# V-00757-01.net
KiCad netlist of a schematic drawn in EAGLE
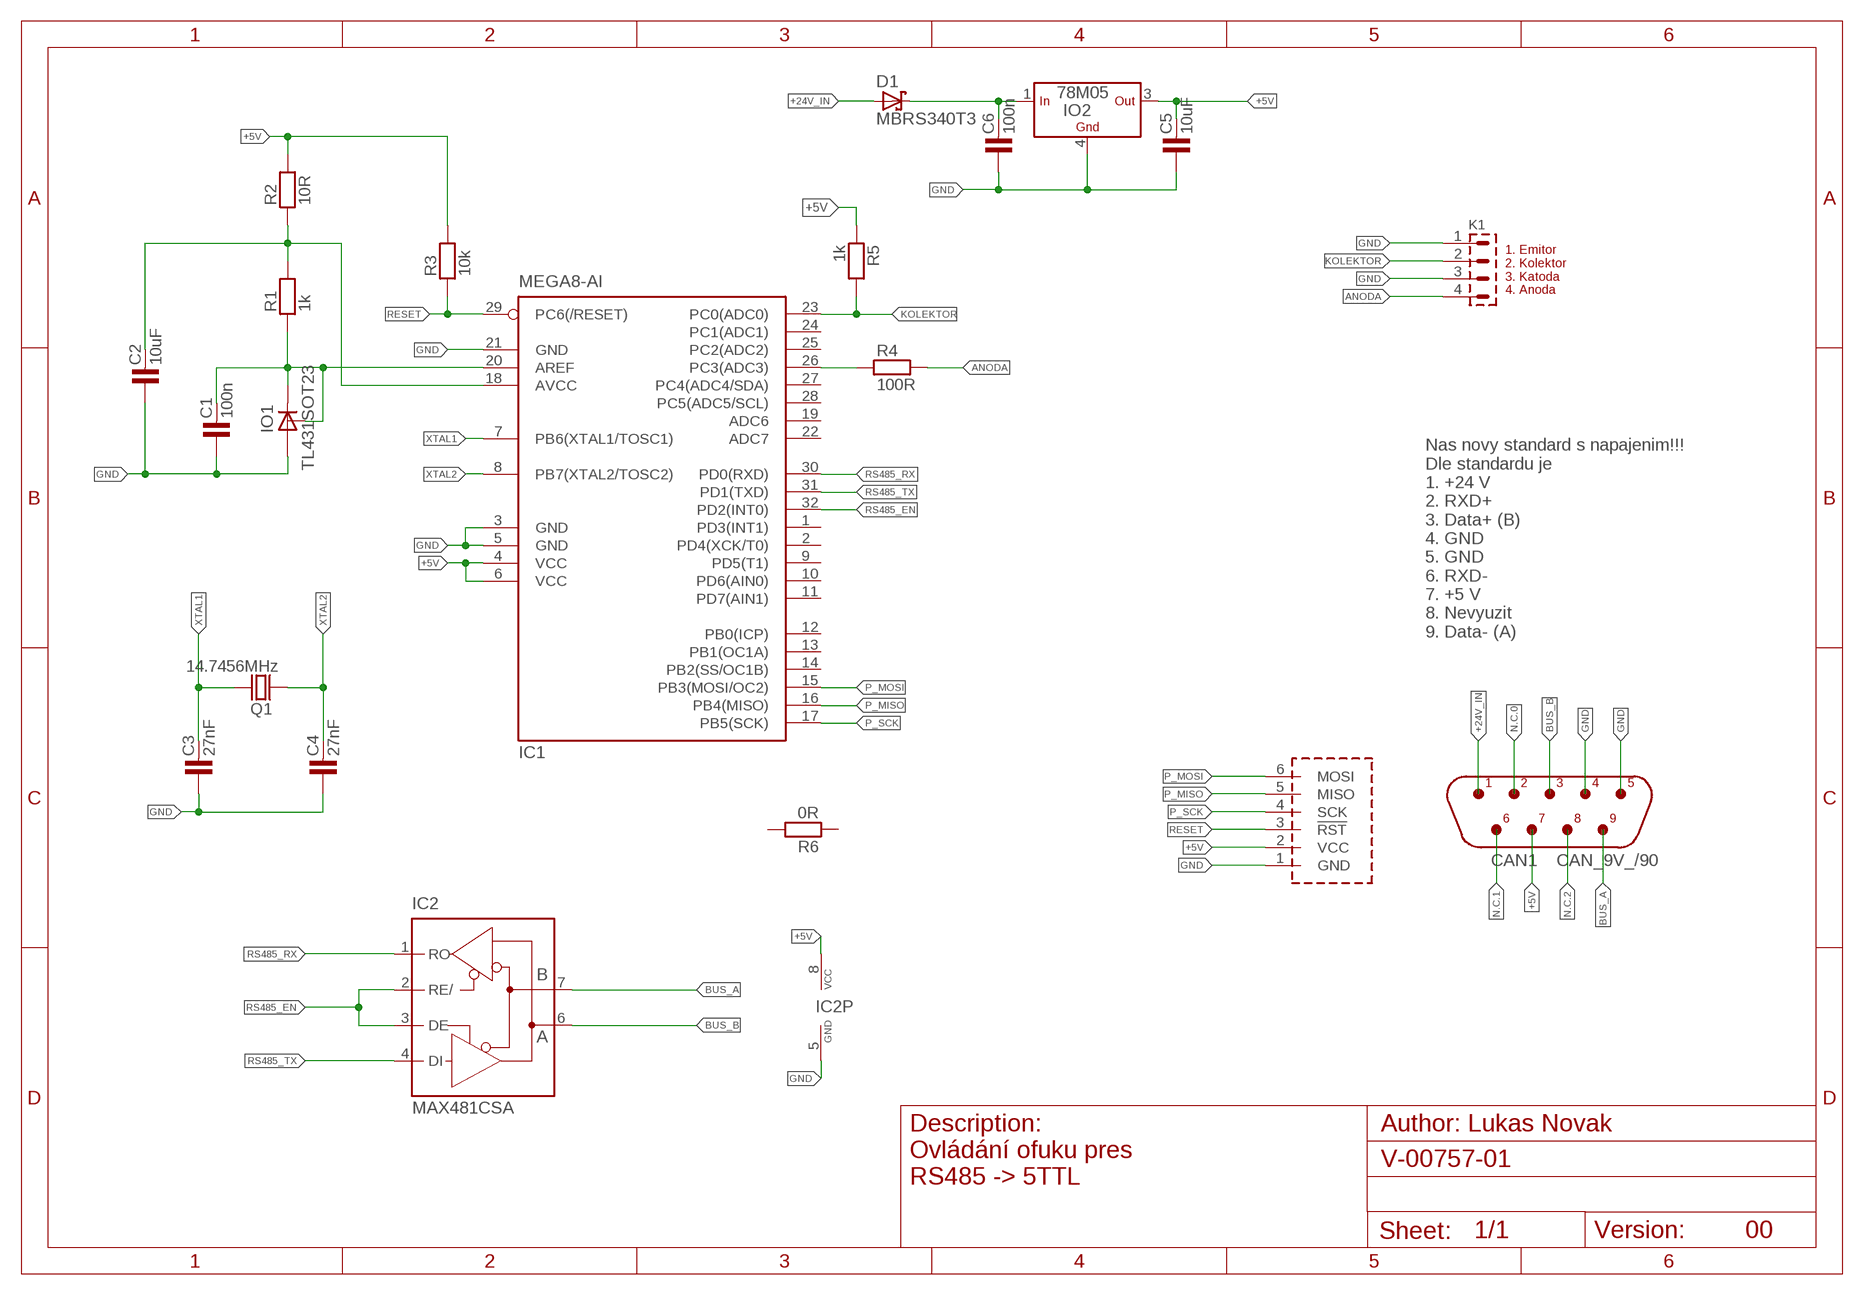
[diagram p0: schematic, sheet 1]

(export (version "E")
  (design (tool "Eeschema 10.0.6"))
  (components
    (comp (ref "C1")
      (value "100n")
      (footprint "eagle-import:1206")
      (libsource (lib "eagle-import") (part "C-KER_1206"))
    )
    (comp (ref "C2")
      (value "10uF")
      (footprint "eagle-import:1206")
      (libsource (lib "eagle-import") (part "C-KER_1206"))
    )
    (comp (ref "C3")
      (value "27nF")
      (footprint "eagle-import:0805")
      (libsource (lib "eagle-import") (part "C-KER_0805"))
    )
    (comp (ref "C4")
      (value "27nF")
      (footprint "eagle-import:0805")
      (libsource (lib "eagle-import") (part "C-KER_0805"))
    )
    (comp (ref "C5")
      (value "10uF")
      (footprint "eagle-import:1206")
      (libsource (lib "eagle-import") (part "C-KER_1206"))
    )
    (comp (ref "C6")
      (value "100n")
      (footprint "eagle-import:1206")
      (libsource (lib "eagle-import") (part "C-KER_1206"))
    )
    (comp (ref "CAN1")
      (value "CAN_9V_/90")
      (footprint "eagle-import:CAN9V_90")
      (libsource (lib "eagle-import") (part "CAN_9V_/90"))
    )
    (comp (ref "D1")
      (value "MBRS340T3")
      (footprint "eagle-import:SMC")
      (libsource (lib "eagle-import") (part "MBRS30T34"))
    )
    (comp (ref "IC1")
      (value "MEGA8-AI")
      (footprint "eagle-import:TQFP32-08")
      (fields (field (name "MPN") "ATMEGA8-16AU"))
      (libsource (lib "eagle-import") (part "MEGA8-AI"))
    )
    (comp (ref "IC2")
      (value "MAX481CSA")
      (footprint "eagle-import:SO08")
      (fields (field (name "MF") "MAXIM"))
      (libsource (lib "eagle-import") (part "MAX481CSA"))
    )
    (comp (ref "IO1")
      (value "TL431SOT23")
      (footprint "eagle-import:SOT23")
      (fields (field (name "MPN") "TL431BFDT"))
      (libsource (lib "eagle-import") (part "TL431SOT23"))
    )
    (comp (ref "IO2")
      (value "78M05")
      (footprint "eagle-import:DPAK")
      (libsource (lib "eagle-import") (part "78?M"))
    )
    (comp (ref "K1")
      (value "PSH02-04W")
      (footprint "eagle-import:PSH02-04W")
      (libsource (lib "eagle-import") (part "PSH02-04W"))
    )
    (comp (ref "Q1")
      (value "14.7456MHz")
      (footprint "eagle-import:HC-49U")
      (libsource (lib "eagle-import") (part "Q_HC-49U"))
    )
    (comp (ref "R1")
      (value "1k")
      (footprint "eagle-import:1206")
      (libsource (lib "eagle-import") (part "R_1206"))
    )
    (comp (ref "R2")
      (value "10R")
      (footprint "eagle-import:1206")
      (libsource (lib "eagle-import") (part "R_1206"))
    )
    (comp (ref "R3")
      (value "10k")
      (footprint "eagle-import:1206")
      (libsource (lib "eagle-import") (part "R_1206"))
    )
    (comp (ref "R4")
      (value "100R")
      (footprint "eagle-import:1206")
      (libsource (lib "eagle-import") (part "R_1206"))
    )
    (comp (ref "R5")
      (value "1k")
      (footprint "eagle-import:1206")
      (libsource (lib "eagle-import") (part "R_1206"))
    )
    (comp (ref "R6")
      (value "0R")
      (footprint "eagle-import:1206")
      (libsource (lib "eagle-import") (part "R_1206"))
    )
    (comp (ref "U$1")
      (value "AVR_PROG_SPI")
      (footprint "eagle-import:PSH02-06P")
      (libsource (lib "eagle-import") (part "AVR_PROG_SPI"))
    )
  )
  (nets
    (net (code "1") (name "+5V") (class "Default")
      (node (ref "C5") (pin "2") (pinfunction "2_2") (pintype "passive"))
      (node (ref "CAN1") (pin "7") (pinfunction "7_7") (pintype "passive"))
      (node (ref "IC1") (pin "4") (pinfunction "VCC_4") (pintype "power_in"))
      (node (ref "IC1") (pin "6") (pinfunction "VCC_6") (pintype "power_in"))
      (node (ref "IC2") (pin "8") (pinfunction "VCC_8") (pintype "power_in"))
      (node (ref "IO2") (pin "3") (pinfunction "OUT_3") (pintype "passive"))
      (node (ref "R2") (pin "2") (pinfunction "2_2") (pintype "passive"))
      (node (ref "R3") (pin "2") (pinfunction "2_2") (pintype "passive"))
      (node (ref "R5") (pin "1") (pinfunction "1_1") (pintype "passive"))
      (node (ref "U$1") (pin "2") (pinfunction "VCC_2") (pintype "bidirectional"))
    )
    (net (code "2") (name "+24V_IN") (class "Default")
      (node (ref "CAN1") (pin "1") (pinfunction "1_1") (pintype "passive"))
      (node (ref "D1") (pin "A") (pinfunction "A_A") (pintype "passive"))
    )
    (net (code "3") (name "ANODA") (class "Default")
      (node (ref "K1") (pin "4") (pinfunction "4_4") (pintype "passive"))
      (node (ref "R4") (pin "2") (pinfunction "2_2") (pintype "passive"))
    )
    (net (code "4") (name "BUS_A") (class "Default")
      (node (ref "CAN1") (pin "9") (pinfunction "9_9") (pintype "passive"))
      (node (ref "IC2") (pin "7") (pinfunction "B_7") (pintype "passive"))
    )
    (net (code "5") (name "BUS_B") (class "Default")
      (node (ref "CAN1") (pin "3") (pinfunction "3_3") (pintype "passive"))
      (node (ref "IC2") (pin "6") (pinfunction "A_6") (pintype "passive"))
    )
    (net (code "6") (name "GND") (class "Default")
      (node (ref "C1") (pin "1") (pinfunction "1_1") (pintype "passive"))
      (node (ref "C2") (pin "1") (pinfunction "1_1") (pintype "passive"))
      (node (ref "C3") (pin "1") (pinfunction "1_1") (pintype "passive"))
      (node (ref "C4") (pin "1") (pinfunction "1_1") (pintype "passive"))
      (node (ref "C5") (pin "1") (pinfunction "1_1") (pintype "passive"))
      (node (ref "C6") (pin "1") (pinfunction "1_1") (pintype "passive"))
      (node (ref "CAN1") (pin "4") (pinfunction "4_4") (pintype "passive"))
      (node (ref "CAN1") (pin "5") (pinfunction "5_5") (pintype "passive"))
      (node (ref "IC1") (pin "21") (pinfunction "GND_21") (pintype "power_in"))
      (node (ref "IC1") (pin "3") (pinfunction "GND_3") (pintype "power_in"))
      (node (ref "IC1") (pin "5") (pinfunction "GND_5") (pintype "power_in"))
      (node (ref "IC2") (pin "5") (pinfunction "GND_5") (pintype "power_in"))
      (node (ref "IO1") (pin "3") (pinfunction "A_3") (pintype "bidirectional"))
      (node (ref "IO2") (pin "4") (pinfunction "GND_4") (pintype "passive"))
      (node (ref "K1") (pin "1") (pinfunction "1_1") (pintype "passive"))
      (node (ref "K1") (pin "3") (pinfunction "3_3") (pintype "passive"))
      (node (ref "U$1") (pin "1") (pinfunction "GND_1") (pintype "bidirectional"))
    )
    (net (code "7") (name "KOLEKTOR") (class "Default")
      (node (ref "IC1") (pin "23") (pinfunction "PC0(ADC0)_23") (pintype "bidirectional"))
      (node (ref "K1") (pin "2") (pinfunction "2_2") (pintype "passive"))
      (node (ref "R5") (pin "2") (pinfunction "2_2") (pintype "passive"))
    )
    (net (code "8") (name "N.C.0") (class "Default")
      (node (ref "CAN1") (pin "2") (pinfunction "2_2") (pintype "passive"))
    )
    (net (code "9") (name "N.C.1") (class "Default")
      (node (ref "CAN1") (pin "6") (pinfunction "6_6") (pintype "passive"))
    )
    (net (code "10") (name "N.C.2") (class "Default")
      (node (ref "CAN1") (pin "8") (pinfunction "8_8") (pintype "passive"))
    )
    (net (code "11") (name "Net-(IC1-AREF)") (class "Default")
      (node (ref "C1") (pin "2") (pinfunction "2_2") (pintype "passive"))
      (node (ref "IC1") (pin "20") (pinfunction "AREF_20") (pintype "passive"))
      (node (ref "IO1") (pin "1") (pinfunction "C_1") (pintype "bidirectional"))
      (node (ref "IO1") (pin "2") (pinfunction "R_2") (pintype "bidirectional"))
      (node (ref "R1") (pin "1") (pinfunction "1_1") (pintype "passive"))
    )
    (net (code "12") (name "Net-(IC1-AVCC)") (class "Default")
      (node (ref "C2") (pin "2") (pinfunction "2_2") (pintype "passive"))
      (node (ref "IC1") (pin "18") (pinfunction "AVCC_18") (pintype "power_in"))
      (node (ref "R1") (pin "2") (pinfunction "2_2") (pintype "passive"))
      (node (ref "R2") (pin "1") (pinfunction "1_1") (pintype "passive"))
    )
    (net (code "13") (name "Net-(IC1-PC3(ADC3))") (class "Default")
      (node (ref "IC1") (pin "26") (pinfunction "PC3(ADC3)_26") (pintype "bidirectional"))
      (node (ref "R4") (pin "1") (pinfunction "1_1") (pintype "passive"))
    )
    (net (code "14") (name "Net-(IO2-IN)") (class "Default")
      (node (ref "C6") (pin "2") (pinfunction "2_2") (pintype "passive"))
      (node (ref "D1") (pin "C") (pinfunction "C_C") (pintype "passive"))
      (node (ref "IO2") (pin "1") (pinfunction "IN_1") (pintype "passive"))
    )
    (net (code "15") (name "P_MISO") (class "Default")
      (node (ref "IC1") (pin "16") (pinfunction "PB4(MISO)_16") (pintype "bidirectional"))
      (node (ref "U$1") (pin "5") (pinfunction "MISO_5") (pintype "bidirectional"))
    )
    (net (code "16") (name "P_MOSI") (class "Default")
      (node (ref "IC1") (pin "15") (pinfunction "PB3(MOSI/OC2)_15") (pintype "bidirectional"))
      (node (ref "U$1") (pin "6") (pinfunction "MOSI_6") (pintype "bidirectional"))
    )
    (net (code "17") (name "P_SCK") (class "Default")
      (node (ref "IC1") (pin "17") (pinfunction "PB5(SCK)_17") (pintype "bidirectional"))
      (node (ref "U$1") (pin "4") (pinfunction "SCK_4") (pintype "bidirectional"))
    )
    (net (code "18") (name "RESET") (class "Default")
      (node (ref "IC1") (pin "29") (pinfunction "PC6(/RESET)_29") (pintype "bidirectional"))
      (node (ref "R3") (pin "1") (pinfunction "1_1") (pintype "passive"))
      (node (ref "U$1") (pin "3") (pinfunction "~{RST}_3") (pintype "bidirectional"))
    )
    (net (code "19") (name "RS485_EN") (class "Default")
      (node (ref "IC1") (pin "32") (pinfunction "PD2(INT0)_32") (pintype "bidirectional"))
      (node (ref "IC2") (pin "2") (pinfunction "RE/_2") (pintype "input"))
      (node (ref "IC2") (pin "3") (pinfunction "DE_3") (pintype "input"))
    )
    (net (code "20") (name "RS485_RX") (class "Default")
      (node (ref "IC1") (pin "30") (pinfunction "PD0(RXD)_30") (pintype "bidirectional"))
      (node (ref "IC2") (pin "1") (pinfunction "RO_1") (pintype "output"))
    )
    (net (code "21") (name "RS485_TX") (class "Default")
      (node (ref "IC1") (pin "31") (pinfunction "PD1(TXD)_31") (pintype "bidirectional"))
      (node (ref "IC2") (pin "4") (pinfunction "DI_4") (pintype "input"))
    )
    (net (code "22") (name "XTAL1") (class "Default")
      (node (ref "C3") (pin "2") (pinfunction "2_2") (pintype "passive"))
      (node (ref "IC1") (pin "7") (pinfunction "PB6(XTAL1/TOSC1)_7") (pintype "bidirectional"))
      (node (ref "Q1") (pin "2") (pinfunction "2_2") (pintype "passive"))
    )
    (net (code "23") (name "XTAL2") (class "Default")
      (node (ref "C4") (pin "2") (pinfunction "2_2") (pintype "passive"))
      (node (ref "IC1") (pin "8") (pinfunction "PB7(XTAL2/TOSC2)_8") (pintype "bidirectional"))
      (node (ref "Q1") (pin "1") (pinfunction "1_1") (pintype "passive"))
    )
    (net (code "24") (name "unconnected-(IC1-ADC6-Pad19)") (class "Default")
      (node (ref "IC1") (pin "19") (pinfunction "ADC6_19") (pintype "bidirectional"))
    )
    (net (code "25") (name "unconnected-(IC1-ADC7-Pad22)") (class "Default")
      (node (ref "IC1") (pin "22") (pinfunction "ADC7_22") (pintype "bidirectional"))
    )
    (net (code "26") (name "unconnected-(IC1-PB0(ICP)-Pad12)") (class "Default")
      (node (ref "IC1") (pin "12") (pinfunction "PB0(ICP)_12") (pintype "bidirectional"))
    )
    (net (code "27") (name "unconnected-(IC1-PB1(OC1A)-Pad13)") (class "Default")
      (node (ref "IC1") (pin "13") (pinfunction "PB1(OC1A)_13") (pintype "bidirectional"))
    )
    (net (code "28") (name "unconnected-(IC1-PB2(SS{slash}OC1B)-Pad14)") (class "Default")
      (node (ref "IC1") (pin "14") (pinfunction "PB2(SS/OC1B)_14") (pintype "bidirectional"))
    )
    (net (code "29") (name "unconnected-(IC1-PC1(ADC1)-Pad24)") (class "Default")
      (node (ref "IC1") (pin "24") (pinfunction "PC1(ADC1)_24") (pintype "bidirectional"))
    )
    (net (code "30") (name "unconnected-(IC1-PC2(ADC2)-Pad25)") (class "Default")
      (node (ref "IC1") (pin "25") (pinfunction "PC2(ADC2)_25") (pintype "bidirectional"))
    )
    (net (code "31") (name "unconnected-(IC1-PC4(ADC4{slash}SDA)-Pad27)") (class "Default")
      (node (ref "IC1") (pin "27") (pinfunction "PC4(ADC4/SDA)_27") (pintype "bidirectional"))
    )
    (net (code "32") (name "unconnected-(IC1-PC5(ADC5{slash}SCL)-Pad28)") (class "Default")
      (node (ref "IC1") (pin "28") (pinfunction "PC5(ADC5/SCL)_28") (pintype "bidirectional"))
    )
    (net (code "33") (name "unconnected-(IC1-PD3(INT1)-Pad1)") (class "Default")
      (node (ref "IC1") (pin "1") (pinfunction "PD3(INT1)_1") (pintype "bidirectional"))
    )
    (net (code "34") (name "unconnected-(IC1-PD4(XCK{slash}T0)-Pad2)") (class "Default")
      (node (ref "IC1") (pin "2") (pinfunction "PD4(XCK/T0)_2") (pintype "bidirectional"))
    )
    (net (code "35") (name "unconnected-(IC1-PD5(T1)-Pad9)") (class "Default")
      (node (ref "IC1") (pin "9") (pinfunction "PD5(T1)_9") (pintype "bidirectional"))
    )
    (net (code "36") (name "unconnected-(IC1-PD6(AIN0)-Pad10)") (class "Default")
      (node (ref "IC1") (pin "10") (pinfunction "PD6(AIN0)_10") (pintype "bidirectional"))
    )
    (net (code "37") (name "unconnected-(IC1-PD7(AIN1)-Pad11)") (class "Default")
      (node (ref "IC1") (pin "11") (pinfunction "PD7(AIN1)_11") (pintype "bidirectional"))
    )
    (net (code "38") (name "unconnected-(R6-Pad1)") (class "Default")
      (node (ref "R6") (pin "1") (pinfunction "1_1") (pintype "passive"))
    )
    (net (code "39") (name "unconnected-(R6-Pad2)") (class "Default")
      (node (ref "R6") (pin "2") (pinfunction "2_2") (pintype "passive"))
    )
  )
)
